# ArbPwrBoost_P4.net
KiCad netlist of a schematic drawn in Altium Designer
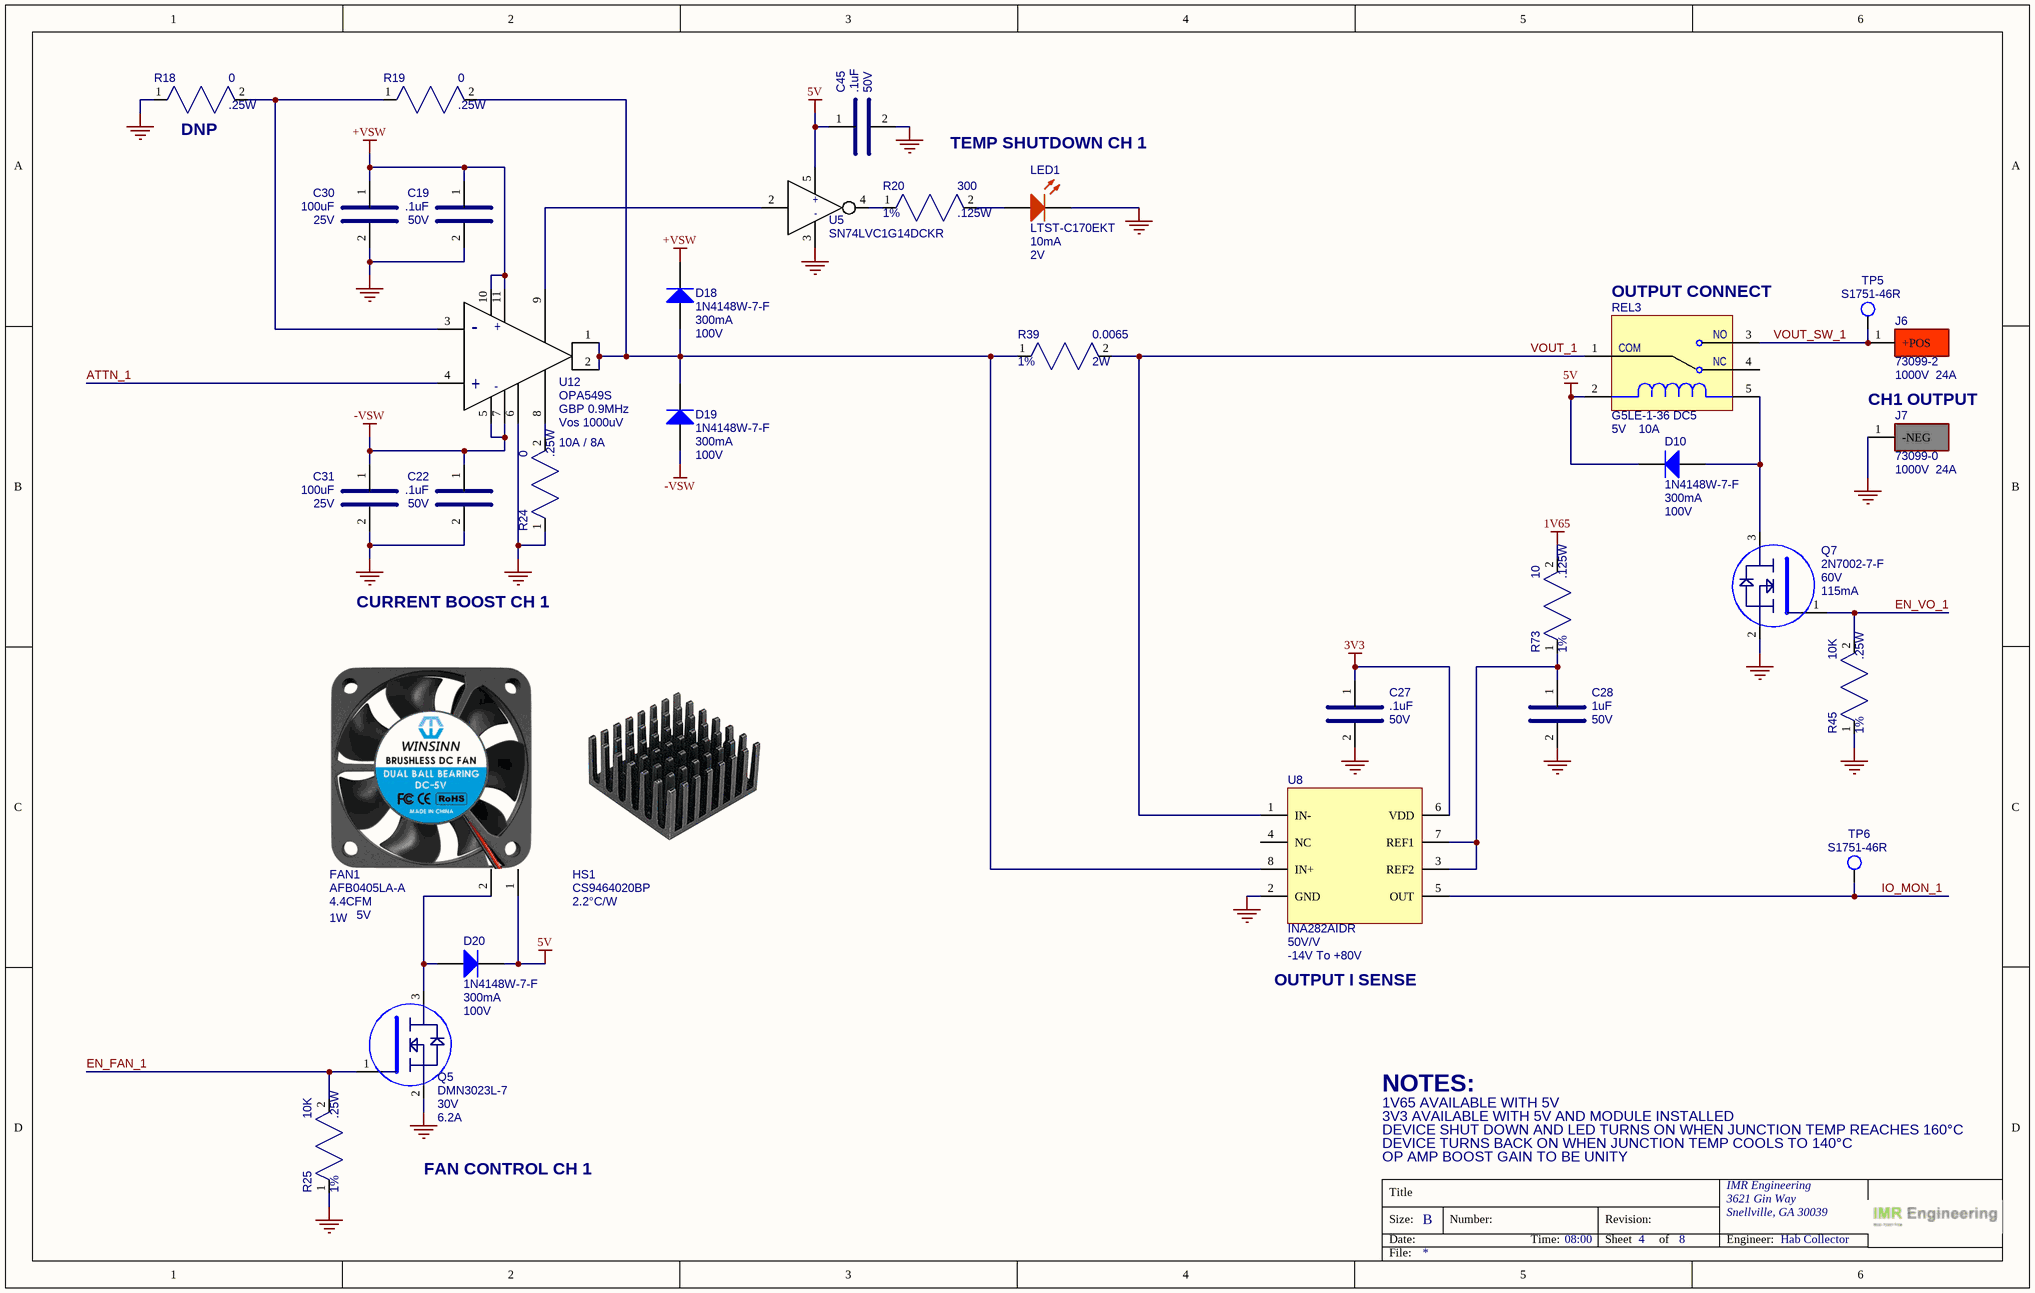
[diagram p0: ArbPwrBoost_P4.SchDoc]

(export (version "E")
  (design (tool "Eeschema 10.0.6"))
  (components
    (comp (ref "C19")
      (value ".1uF")
      (footprint "CAP_0805")
      (description "CAP CER 0.1UF 50V X7R 0805")
      (fields
        (field (name "MFG") "KYOCERA AVX")
        (field (name "VOLTAGE") "50V")
        (field (name "Comment") "KGM21NR71H104KT")
      )
      (libsource (lib "IMR_LIB_SCH_R2") (part "CAP_SMD_0.1UF_50V_0805"))
    )
    (comp (ref "C22")
      (value ".1uF")
      (footprint "CAP_0805")
      (description "CAP CER 0.1UF 50V X7R 0805")
      (fields
        (field (name "MFG") "KYOCERA AVX")
        (field (name "VOLTAGE") "50V")
        (field (name "Comment") "KGM21NR71H104KT")
      )
      (libsource (lib "IMR_LIB_SCH_R2") (part "CAP_SMD_0.1UF_50V_0805"))
    )
    (comp (ref "C27")
      (value ".1uF")
      (footprint "CAP_0805")
      (description "CAP CER 0.1UF 50V X7R 0805")
      (fields
        (field (name "MFG") "KYOCERA AVX")
        (field (name "VOLTAGE") "50V")
        (field (name "Comment") "KGM21NR71H104KT")
      )
      (libsource (lib "IMR_LIB_SCH_R2") (part "CAP_SMD_0.1UF_50V_0805"))
    )
    (comp (ref "C28")
      (value "1uF")
      (footprint "CAP_0805")
      (description "CAP CER 1UF 50V X7R 0805")
      (fields
        (field (name "MFG") "KYOCERA AVX")
        (field (name "VOLTAGE") "50V")
        (field (name "Comment") "08055C105K4T2A")
      )
      (libsource (lib "IMR_LIB_SCH_R2") (part "CAP_SMD_1UF_50V_0805"))
    )
    (comp (ref "C30")
      (value "100uF")
      (footprint "CAPC6153X670N")
      (description "CAP CER 100UF 25V X7S SMD")
      (fields
        (field (name "MFG") "Murata Electronics")
        (field (name "VOLTAGE") "25V")
        (field (name "Comment") "KCM55WC71E107MH13L")
      )
      (libsource (lib "IMR_LIB_SCH_R2") (part "CAP_SMD_100UF_25V_SMD"))
    )
    (comp (ref "C31")
      (value "100uF")
      (footprint "CAPC6153X670N")
      (description "CAP CER 100UF 25V X7S SMD")
      (fields
        (field (name "MFG") "Murata Electronics")
        (field (name "VOLTAGE") "25V")
        (field (name "Comment") "KCM55WC71E107MH13L")
      )
      (libsource (lib "IMR_LIB_SCH_R2") (part "CAP_SMD_100UF_25V_SMD"))
    )
    (comp (ref "C45")
      (value ".1uF")
      (footprint "CAP_0805")
      (description "CAP CER 0.1UF 50V X7R 0805")
      (fields
        (field (name "MFG") "KYOCERA AVX")
        (field (name "VOLTAGE") "50V")
        (field (name "Comment") "KGM21NR71H104KT")
      )
      (libsource (lib "IMR_LIB_SCH_R2") (part "CAP_SMD_0.1UF_50V_0805"))
    )
    (comp (ref "D10")
      (value "100V")
      (footprint "SOD123")
      (description "RELAY REED SPDT 250MA 5V")
      (fields
        (field (name "MFG") "Diodes Inc")
        (field (name "MFG_PN") "1N4148W-7-F")
        (field (name "CURRENT") "300mA")
        (field (name "Comment") "1N4148W-7-F")
      )
      (libsource (lib "IMR_LIB_SCH_R2") (part "DIODE_1N4148W-7-F"))
    )
    (comp (ref "D18")
      (value "100V")
      (footprint "SOD123")
      (description "RELAY REED SPDT 250MA 5V")
      (fields
        (field (name "MFG") "Diodes Inc")
        (field (name "MFG_PN") "1N4148W-7-F")
        (field (name "CURRENT") "300mA")
        (field (name "Comment") "1N4148W-7-F")
      )
      (libsource (lib "IMR_LIB_SCH_R2") (part "DIODE_1N4148W-7-F"))
    )
    (comp (ref "D19")
      (value "100V")
      (footprint "SOD123")
      (description "RELAY REED SPDT 250MA 5V")
      (fields
        (field (name "MFG") "Diodes Inc")
        (field (name "MFG_PN") "1N4148W-7-F")
        (field (name "CURRENT") "300mA")
        (field (name "Comment") "1N4148W-7-F")
      )
      (libsource (lib "IMR_LIB_SCH_R2") (part "DIODE_1N4148W-7-F"))
    )
    (comp (ref "D20")
      (value "100V")
      (footprint "SOD123")
      (description "RELAY REED SPDT 250MA 5V")
      (fields
        (field (name "MFG") "Diodes Inc")
        (field (name "MFG_PN") "1N4148W-7-F")
        (field (name "CURRENT") "300mA")
        (field (name "Comment") "1N4148W-7-F")
      )
      (libsource (lib "IMR_LIB_SCH_R2") (part "DIODE_1N4148W-7-F"))
    )
    (comp (ref "FAN1")
      (value "AFB0405LA-A")
      (footprint "FAN_AFB0405LA-A")
      (description "FAN AXIAL 40X10MM BALL 5VDC WIRE")
      (fields
        (field (name "MFG") "Delta Electronicis")
        (field (name "MFG_PN") "AFB0405LA-A")
        (field (name "AIR FLOW") "4.4CFM")
        (field (name "VOLTAGE") "5V")
        (field (name "POWER") "1W")
      )
      (libsource (lib "IMR_LIB_SCH_R2") (part "FAN_AFB0405LA-A"))
    )
    (comp (ref "HS1")
      (value "CS9464020BP")
      (footprint "HEATSINK_CS9464020BP")
      (description "Heat Sink Aluminum Top Mount")
      (fields
        (field (name "MFG") "Cooling Source")
        (field (name "MFG_PN") "CS9464020BP")
        (field (name "THERMAL RESISTANCE") "2.2°C/W")
      )
      (libsource (lib "IMR_LIB_SCH_R2") (part "HEATSINK_CS9464020BP"))
    )
    (comp (ref "J6")
      (value "1000V")
      (footprint "Pomona_73099-2")
      (description "CONN 4mm Banana Socket Right Angle PCB RED")
      (fields
        (field (name "MFG") "Pomona")
        (field (name "MFG_PN") "73099-2")
        (field (name "CURRENT") "24A")
        (field (name "Comment") "73099-2")
      )
      (libsource (lib "IMR_LIB_SCH_R2") (part "CONN_PANOMA_73099-2"))
    )
    (comp (ref "J7")
      (value "1000V")
      (footprint "Pomona_73099-0")
      (description "CONN 4mm Banana Socket Right Angle PCB BLK")
      (fields
        (field (name "MFG") "Pomona")
        (field (name "MFG_PN") "73099-0")
        (field (name "CURRENT") "24A")
        (field (name "Comment") "73099-0")
      )
      (libsource (lib "IMR_LIB_SCH_R2") (part "CONN_PANOMA_73099-0"))
    )
    (comp (ref "LED1")
      (value "2V")
      (footprint "LED_0805")
      (description "LED RED CLEAR SMD")
      (fields
        (field (name "MFG") "Diodes Inc")
        (field (name "MFG_PN") "LTST-C170EKT")
        (field (name "CURRENT") "10mA")
        (field (name "Comment") "LTST-C170EKT")
      )
      (libsource (lib "IMR_LIB_SCH_R2") (part "LED_RED_LTST-C170EKT"))
    )
    (comp (ref "Q5")
      (value "30V")
      (footprint "SOT-23")
      (description "MOSFET N-CH 30V 6.2A SOT23-3")
      (fields
        (field (name "MFG") "Diodes Inc")
        (field (name "MFG_PN") "DMN3023L-7")
        (field (name "CURRENT") "6.2A")
        (field (name "Comment") "DMN3023L-7")
      )
      (libsource (lib "IMR_LIB_SCH_R2") (part "MOSFET_NCH_DMN3023L-7"))
    )
    (comp (ref "Q7")
      (value "60V")
      (footprint "SOT-23")
      (description "MOSFET N-CH 60V 115MA SOT23-3")
      (fields
        (field (name "MFG") "Diodes Inc")
        (field (name "MFG_PN") "2N7002-7-F")
        (field (name "CURRENT") "115mA")
        (field (name "Comment") "2N7002-7-F")
      )
      (libsource (lib "IMR_LIB_SCH_R2") (part "MOSFET_NCH_2N7002-7-F"))
    )
    (comp (ref "R18")
      (value "0")
      (footprint "RES_0805")
      (description "RES SMD 0 OHM 1% 1/8W 0805")
      (fields (field (name "MFG") "Yageo") (field (name "TOLERANCE") "1%") (field (name "POWER") ".25W"))
      (libsource (lib "IMR_LIB_SCH_R2") (part "RES_SMD_0_0805_1/8W_1%"))
    )
    (comp (ref "R19")
      (value "0")
      (footprint "RES_0805")
      (description "RES SMD 0 OHM 1% 1/8W 0805")
      (fields (field (name "MFG") "Yageo") (field (name "TOLERANCE") "1%") (field (name "POWER") ".25W"))
      (libsource (lib "IMR_LIB_SCH_R2") (part "RES_SMD_0_0805_1/8W_1%"))
    )
    (comp (ref "R20")
      (value "300")
      (footprint "RES_0805")
      (description "RES SMD 300 OHM 1% 1/8W 0805")
      (fields
        (field (name "MFG") "Yageo")
        (field (name "POWER") ".125W")
        (field (name "TOLERANCE") "1%")
        (field (name "Comment") "RC0805FR-07300RL")
      )
      (libsource (lib "IMR_LIB_SCH_R2") (part "RES_SMD_300_0805_1/8W_1%"))
    )
    (comp (ref "R24")
      (value "0")
      (footprint "RES_0805")
      (description "RES SMD 0 OHM 1% 1/8W 0805")
      (fields (field (name "MFG") "Yageo") (field (name "TOLERANCE") "1%") (field (name "POWER") ".25W"))
      (libsource (lib "IMR_LIB_SCH_R2") (part "RES_SMD_0_0805_1/8W_1%"))
    )
    (comp (ref "R25")
      (value "10K")
      (footprint "RES_0805")
      (description "RES SMD 10K OHM 1% 1/4W 0805")
      (fields
        (field (name "MFG") "Yageo")
        (field (name "POWER") ".25W")
        (field (name "TOLERANCE") "1%")
        (field (name "Comment") "RC0805FR-7W10KL")
      )
      (libsource (lib "IMR_LIB_SCH_R2") (part "RES_SMD_10K_0805_1/4W_1%"))
    )
    (comp (ref "R39")
      (value "0.0065")
      (footprint "RES_2512")
      (description "RES SMD 0.0065 OHM 1% 2W 2512")
      (fields
        (field (name "MFG") "Vishay Dale")
        (field (name "TOLERANCE") "1%")
        (field (name "POWER") "2W")
        (field (name "Comment") "WSL25126L500FEA18")
      )
      (libsource (lib "IMR_LIB_SCH_R2") (part "RES_SMD_0.0065_2512_2W_1%"))
    )
    (comp (ref "R45")
      (value "10K")
      (footprint "RES_0805")
      (description "RES SMD 10K OHM 1% 1/4W 0805")
      (fields
        (field (name "MFG") "Yageo")
        (field (name "POWER") ".25W")
        (field (name "TOLERANCE") "1%")
        (field (name "Comment") "RC0805FR-7W10KL")
      )
      (libsource (lib "IMR_LIB_SCH_R2") (part "RES_SMD_10K_0805_1/4W_1%"))
    )
    (comp (ref "R73")
      (value "10")
      (footprint "RES_0805")
      (description "RES SMD 10 OHM 1% 1/8W 0805")
      (fields
        (field (name "MFG") "Yageo")
        (field (name "POWER") ".125W")
        (field (name "TOLERANCE") "1%")
        (field (name "Comment") "RC0805FR-1310RL")
      )
      (libsource (lib "IMR_LIB_SCH_R2") (part "RES_SMD_10_0805_1/8W_1%"))
    )
    (comp (ref "REL3")
      (value "5V")
      (footprint "G5LE")
      (description "RELAY GEN PURPOSE SPDT 10A 5V")
      (fields
        (field (name "MFG") "Omron")
        (field (name "MFG_PN") "G5LE-1-36 DC5")
        (field (name "CURRENT") "10A")
        (field (name "Comment") "G5LE-1-36 DC5")
      )
      (libsource (lib "IMR_LIB_SCH_R2") (part "RELAY_G5LE-1-36 DC5"))
    )
    (comp (ref "TP5")
      (value "S1751-46R")
      (footprint "HARWIN_S1751")
      (description "PCB TEST POINT CONNECT")
      (fields (field (name "MFG") "Harwin Inc") (field (name "MFG_PN") "S1751-46R"))
      (libsource (lib "IMR_LIB_SCH_R2") (part "CONN_TEST_POINT_S1751-46R"))
    )
    (comp (ref "TP6")
      (value "S1751-46R")
      (footprint "HARWIN_S1751")
      (description "PCB TEST POINT CONNECT")
      (fields (field (name "MFG") "Harwin Inc") (field (name "MFG_PN") "S1751-46R"))
      (libsource (lib "IMR_LIB_SCH_R2") (part "CONN_TEST_POINT_S1751-46R"))
    )
    (comp (ref "U5")
      (value "SN74LVC1G14DCKR")
      (footprint "SOT-353")
      (description "IC INVERT SCHMITT 1CH 1IN SC70-5")
      (fields (field (name "MFG") "Texas Instruments") (field (name "MFG_PN") "SN74LVC1G14DCKR"))
      (libsource (lib "IMR_LIB_SCH_R2") (part "IC_SN74LVC1G14DCKR"))
    )
    (comp (ref "U8")
      (value "50V/V")
      (footprint "SOIC-8_54")
      (description "IC CURRENT SENSE 0.4% 50V/V SOIC-8")
      (fields
        (field (name "MFG") "Texas Instruments")
        (field (name "COMMON MODE") "-14V To +80V")
        (field (name "MFG_PN") "INA282AIDR")
        (field (name "Comment") "INA282AIDR")
      )
      (libsource (lib "IMR_LIB_SCH_R2") (part "IC_INA282AIDR"))
    )
    (comp (ref "U12")
      (value "GBP 0.9MHz")
      (footprint "POWER_PACKAGE_11")
      (description "IC OPAMP POWER 1 CIRC 11PWRPACK")
      (fields
        (field (name "MFG") "Texas Instruments")
        (field (name "MFG_PN") "OPA549S")
        (field (name "VOS") "Vos 1000uV")
        (field (name "PEAK / CONTINEOUS CURRENT") "10A / 8A")
        (field (name "Comment") "OPA549S")
      )
      (libsource (lib "IMR_LIB_SCH_R2") (part "OPAMP_OPA549S"))
    )
  )
  (nets
    (net (code "1") (name "+VSW") (class "Default")
      (node (ref "C19") (pin "1") (pinfunction "1_1") (pintype "passive"))
      (node (ref "C30") (pin "1") (pinfunction "1_1") (pintype "passive"))
      (node (ref "D18") (pin "2") (pinfunction "K_2") (pintype "passive"))
      (node (ref "U12") (pin "10") (pintype "passive"))
      (node (ref "U12") (pin "11") (pintype "passive"))
    )
    (net (code "2") (name "-VSW") (class "Default")
      (node (ref "C22") (pin "1") (pinfunction "1_1") (pintype "passive"))
      (node (ref "C31") (pin "1") (pinfunction "1_1") (pintype "passive"))
      (node (ref "D19") (pin "1") (pinfunction "A_1") (pintype "passive"))
      (node (ref "U12") (pin "5") (pintype "passive"))
      (node (ref "U12") (pin "7") (pintype "passive"))
    )
    (net (code "3") (name "/ATTN_1") (class "Default")
      (node (ref "U12") (pin "4") (pinfunction "+_4") (pintype "passive"))
    )
    (net (code "4") (name "/EN_FAN_1") (class "Default")
      (node (ref "Q5") (pin "1") (pinfunction "B_1") (pintype "passive"))
      (node (ref "R25") (pin "2") (pinfunction "2_2") (pintype "passive"))
    )
    (net (code "5") (name "/EN_VO_1") (class "Default")
      (node (ref "Q7") (pin "1") (pinfunction "B_1") (pintype "passive"))
      (node (ref "R45") (pin "2") (pinfunction "2_2") (pintype "passive"))
    )
    (net (code "6") (name "/IO_MON_1") (class "Default")
      (node (ref "TP6") (pin "1") (pintype "passive"))
      (node (ref "U8") (pin "5") (pinfunction "OUT_5") (pintype "passive"))
    )
    (net (code "7") (name "/VOUT_1") (class "Default")
      (node (ref "R39") (pin "2") (pinfunction "2_2") (pintype "passive"))
      (node (ref "REL3") (pin "1") (pinfunction "COM_1") (pintype "passive"))
      (node (ref "U8") (pin "1") (pinfunction "IN-_1") (pintype "passive"))
    )
    (net (code "8") (name "/VOUT_SW_1") (class "Default")
      (node (ref "J6") (pin "1") (pinfunction "+POS_1") (pintype "passive"))
      (node (ref "REL3") (pin "3") (pinfunction "NO_3") (pintype "passive"))
      (node (ref "TP5") (pin "1") (pintype "passive"))
    )
    (net (code "9") (name "1V65") (class "Default")
      (node (ref "R73") (pin "2") (pinfunction "2_2") (pintype "passive"))
    )
    (net (code "10") (name "3V3") (class "Default")
      (node (ref "C27") (pin "1") (pinfunction "1_1") (pintype "passive"))
      (node (ref "U8") (pin "6") (pinfunction "VDD_6") (pintype "passive"))
    )
    (net (code "11") (name "5V") (class "Default")
      (node (ref "C45") (pin "1") (pinfunction "1_1") (pintype "passive"))
      (node (ref "D10") (pin "2") (pinfunction "K_2") (pintype "passive"))
      (node (ref "D20") (pin "2") (pinfunction "K_2") (pintype "passive"))
      (node (ref "FAN1") (pin "1") (pinfunction "1_1") (pintype "passive"))
      (node (ref "REL3") (pin "2") (pintype "passive"))
      (node (ref "U5") (pin "5") (pintype "passive"))
    )
    (net (code "12") (name "GND") (class "Default")
      (node (ref "C19") (pin "2") (pinfunction "2_2") (pintype "passive"))
      (node (ref "C22") (pin "2") (pinfunction "2_2") (pintype "passive"))
      (node (ref "C27") (pin "2") (pinfunction "2_2") (pintype "passive"))
      (node (ref "C28") (pin "2") (pinfunction "2_2") (pintype "passive"))
      (node (ref "C30") (pin "2") (pinfunction "2_2") (pintype "passive"))
      (node (ref "C31") (pin "2") (pinfunction "2_2") (pintype "passive"))
      (node (ref "C45") (pin "2") (pinfunction "2_2") (pintype "passive"))
      (node (ref "J7") (pin "1") (pinfunction "-NEG_1") (pintype "passive"))
      (node (ref "LED1") (pin "K") (pinfunction "K_K") (pintype "passive"))
      (node (ref "Q5") (pin "2") (pinfunction "E_2") (pintype "passive"))
      (node (ref "Q7") (pin "2") (pinfunction "E_2") (pintype "passive"))
      (node (ref "R18") (pin "1") (pinfunction "1_1") (pintype "passive"))
      (node (ref "R24") (pin "1") (pinfunction "1_1") (pintype "passive"))
      (node (ref "R25") (pin "1") (pinfunction "1_1") (pintype "passive"))
      (node (ref "R45") (pin "1") (pinfunction "1_1") (pintype "passive"))
      (node (ref "U12") (pin "6") (pintype "passive"))
      (node (ref "U5") (pin "3") (pintype "passive"))
      (node (ref "U8") (pin "2") (pinfunction "GND_2") (pintype "passive"))
    )
    (net (code "13") (name "Net-(D10-A)") (class "Default")
      (node (ref "D10") (pin "1") (pinfunction "A_1") (pintype "passive"))
      (node (ref "Q7") (pin "3") (pinfunction "C_3") (pintype "passive"))
      (node (ref "REL3") (pin "5") (pintype "passive"))
    )
    (net (code "14") (name "Net-(D18-A)") (class "Default")
      (node (ref "D18") (pin "1") (pinfunction "A_1") (pintype "passive"))
      (node (ref "D19") (pin "2") (pinfunction "K_2") (pintype "passive"))
      (node (ref "R19") (pin "2") (pinfunction "2_2") (pintype "passive"))
      (node (ref "R39") (pin "1") (pinfunction "1_1") (pintype "passive"))
      (node (ref "U12") (pin "1") (pintype "passive"))
      (node (ref "U12") (pin "2") (pintype "passive"))
      (node (ref "U8") (pin "8") (pinfunction "IN+_8") (pintype "passive"))
    )
    (net (code "15") (name "Net-(D20-A)") (class "Default")
      (node (ref "D20") (pin "1") (pinfunction "A_1") (pintype "passive"))
      (node (ref "FAN1") (pin "2") (pinfunction "2_2") (pintype "passive"))
      (node (ref "Q5") (pin "3") (pinfunction "C_3") (pintype "passive"))
    )
    (net (code "16") (name "Net-(LED1-PadA)") (class "Default")
      (node (ref "LED1") (pin "A") (pinfunction "A_A") (pintype "passive"))
      (node (ref "R20") (pin "2") (pinfunction "2_2") (pintype "passive"))
    )
    (net (code "17") (name "Net-(R24-Pad2)") (class "Default")
      (node (ref "R24") (pin "2") (pinfunction "2_2") (pintype "passive"))
      (node (ref "U12") (pin "8") (pintype "passive"))
    )
    (net (code "18") (name "Net-(U5-A)") (class "Default")
      (node (ref "U12") (pin "9") (pintype "passive"))
      (node (ref "U5") (pin "2") (pinfunction "A_2") (pintype "passive"))
    )
    (net (code "19") (name "Net-(U5-Y)") (class "Default")
      (node (ref "R20") (pin "1") (pinfunction "1_1") (pintype "passive"))
      (node (ref "U5") (pin "4") (pinfunction "Y_4") (pintype "passive"))
    )
    (net (code "20") (name "Net-(U8-REF1)") (class "Default")
      (node (ref "C28") (pin "1") (pinfunction "1_1") (pintype "passive"))
      (node (ref "R73") (pin "1") (pinfunction "1_1") (pintype "passive"))
      (node (ref "U8") (pin "3") (pinfunction "REF2_3") (pintype "passive"))
      (node (ref "U8") (pin "7") (pinfunction "REF1_7") (pintype "passive"))
    )
    (net (code "21") (name "Net-(U12--)") (class "Default")
      (node (ref "R18") (pin "2") (pinfunction "2_2") (pintype "passive"))
      (node (ref "R19") (pin "1") (pinfunction "1_1") (pintype "passive"))
      (node (ref "U12") (pin "3") (pinfunction "-_3") (pintype "passive"))
    )
    (net (code "22") (name "unconnected-(REL3-NC-Pad4)") (class "Default")
      (node (ref "REL3") (pin "4") (pinfunction "NC_4") (pintype "passive"))
    )
    (net (code "23") (name "unconnected-(U8-NC-Pad4)") (class "Default")
      (node (ref "U8") (pin "4") (pinfunction "NC_4") (pintype "passive"))
    )
  )
)
